# WlPK1_main.net
KiCad netlist of a schematic drawn in Altium Designer
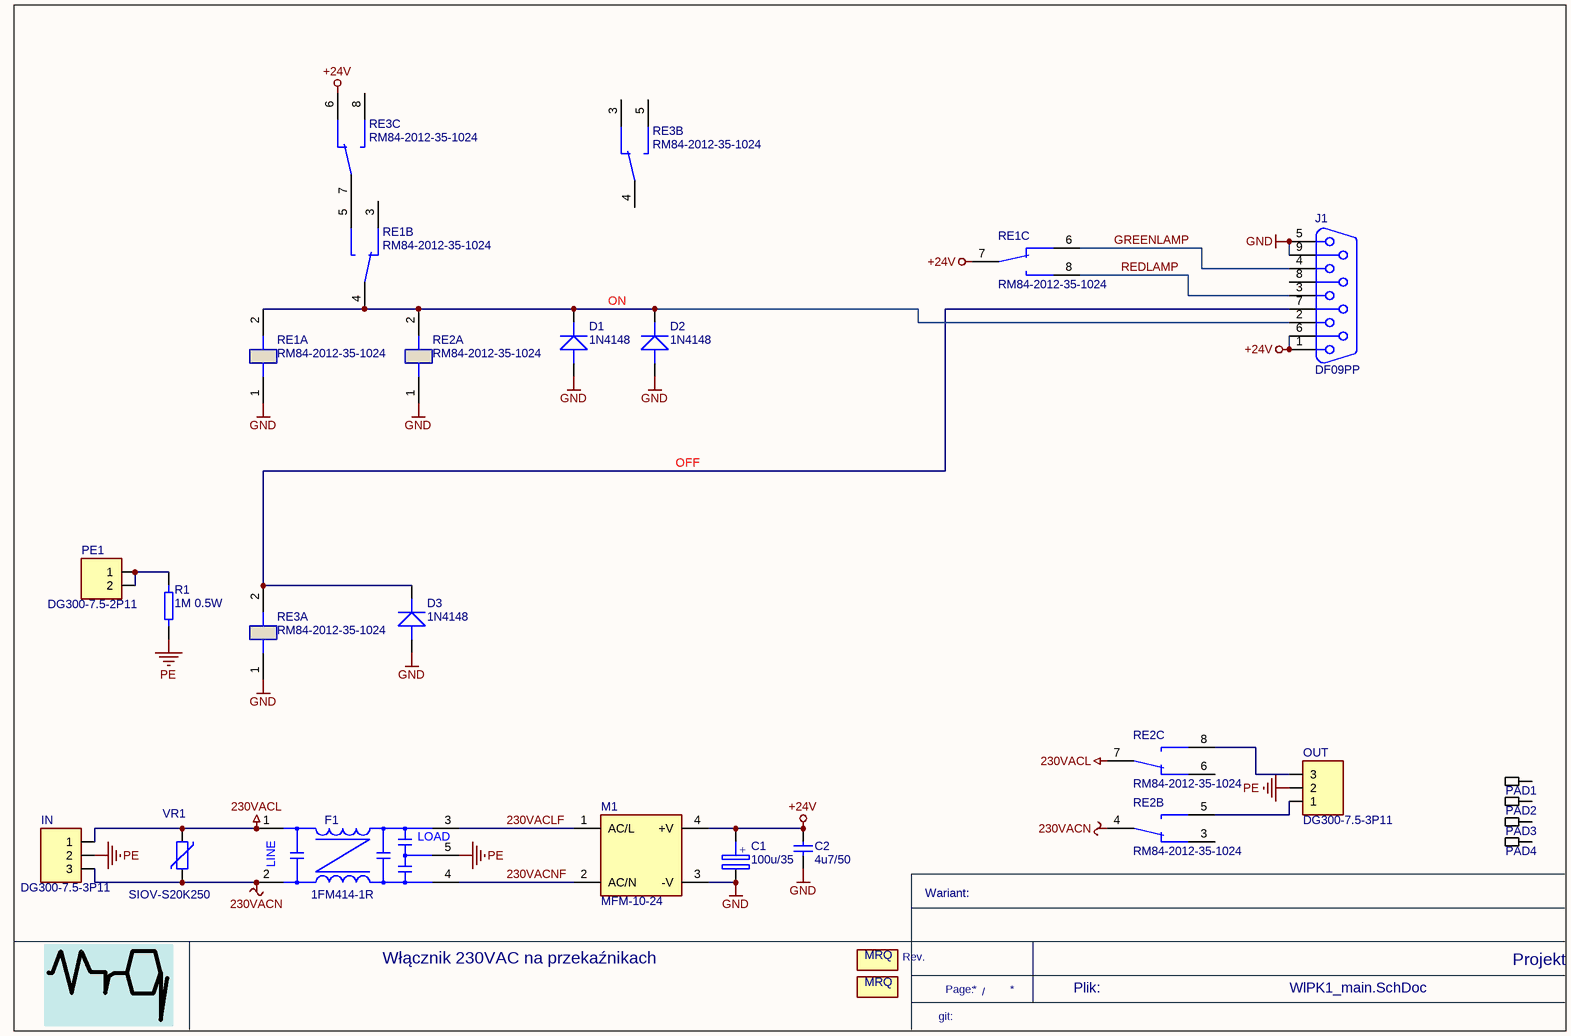
[diagram p0: WlPK1_main.SchDoc]

(export (version "E")
  (design (tool "Eeschema 10.0.6"))
  (components
    (comp (ref "C1") (value "100u/35") (footprint "CE1028") (libsource (lib "PartsMySQL") (part "CEL")))
    (comp (ref "C2") (value "4u7/50") (footprint "1210") (libsource (lib "PartsMySQL") (part "C")))
    (comp (ref "D1") (value "1N4148") (footprint "CE02") (libsource (lib "PartsMySQL") (part "DIODE")))
    (comp (ref "D2") (value "1N4148") (footprint "CE02") (libsource (lib "PartsMySQL") (part "DIODE")))
    (comp (ref "D3") (value "1N4148") (footprint "CE02") (libsource (lib "PartsMySQL") (part "DIODE")))
    (comp (ref "F1") (value "1FM414-1R") (footprint "1FM414") (libsource (lib "PartsMySQL") (part "1FM414")))
    (comp (ref "IN")
      (value "DG300-7.5-3P11")
      (footprint "DG300-7.5-3P11")
      (libsource (lib "") (part "HEADER3_1"))
    )
    (comp (ref "J1") (value "DF09PP") (footprint "DB9/F") (libsource (lib "PartsMySQL") (part "DB9")))
    (comp (ref "LOGO1")
      (value "MRQ_5")
      (footprint "MRQ_5_TL")
      (libsource (lib "PartsMySQL") (part "MRQLOGO"))
    )
    (comp (ref "LOGO2")
      (value "MRQ_5")
      (footprint "MRQ_5_TL")
      (libsource (lib "PartsMySQL") (part "MRQLOGO"))
    )
    (comp (ref "M1")
      (value "MFM-10-24")
      (footprint "MFM-10-24")
      (libsource (lib "PartsMySQL") (part "PM-10-5"))
    )
    (comp (ref "OUT")
      (value "DG300-7.5-3P11")
      (footprint "DG300-7.5-3P11")
      (libsource (lib "PartsMySQL") (part "HEADER3"))
    )
    (comp (ref "PAD1")
      (value "PAD3_5MM")
      (footprint "PAD3_5MM")
      (libsource (lib "PartsMySQL") (part "CLAMP_NOBOM"))
    )
    (comp (ref "PAD2")
      (value "PAD3_5MM")
      (footprint "PAD3_5MM")
      (libsource (lib "PartsMySQL") (part "CLAMP_NOBOM"))
    )
    (comp (ref "PAD3")
      (value "PAD3_5MM")
      (footprint "PAD3_5MM")
      (libsource (lib "PartsMySQL") (part "CLAMP_NOBOM"))
    )
    (comp (ref "PAD4")
      (value "PAD3_5MM")
      (footprint "PAD3_5MM")
      (libsource (lib "PartsMySQL") (part "CLAMP_NOBOM"))
    )
    (comp (ref "PE1")
      (value "DG300-7.5-2P11")
      (footprint "DG300-7.5-2P11")
      (libsource (lib "PartsMySQL") (part "HEADER2"))
    )
    (comp (ref "R1") (value "1M 0.5W") (footprint "R502816") (libsource (lib "PartsMySQL") (part "R")))
    (comp (ref "RE1") (value "RM84-2012-35-1024") (footprint "RM84-P") (libsource (lib "") (part "RM84-P_1")))
    (comp (ref "RE2")
      (value "RM84-2012-35-1024")
      (footprint "RM84-P")
      (libsource (lib "PartsMySQL") (part "RM84-P"))
    )
    (comp (ref "RE3")
      (value "RM84-2012-35-1024")
      (footprint "RM84-P")
      (libsource (lib "PartsMySQL") (part "RM84-P"))
    )
    (comp (ref "VR1")
      (value "SIOV-S20K250")
      (footprint "SIOV-S20K275")
      (libsource (lib "PartsMySQL") (part "VARISTOR"))
    )
  )
  (nets
    (net (code "1") (name "+24V") (class "Default")
      (node (ref "C1") (pin "2") (pinfunction "2_2") (pintype "passive"))
      (node (ref "C2") (pin "1") (pinfunction "1_1") (pintype "passive"))
      (node (ref "J1") (pin "1") (pinfunction "1_1") (pintype "passive"))
      (node (ref "J1") (pin "6") (pinfunction "6_6") (pintype "passive"))
      (node (ref "M1") (pin "4") (pinfunction "+V_4") (pintype "passive"))
      (node (ref "RE1") (pin "7") (pinfunction "11_7") (pintype "passive"))
      (node (ref "RE3") (pin "6") (pinfunction "12_6") (pintype "passive"))
    )
    (net (code "2") (name "/230VACLF") (class "Default")
      (node (ref "F1") (pin "3") (pinfunction "OUT2_3") (pintype "passive"))
      (node (ref "M1") (pin "1") (pinfunction "AC/L_1") (pintype "passive"))
    )
    (net (code "3") (name "/230VACNF") (class "Default")
      (node (ref "F1") (pin "4") (pinfunction "OUT1_4") (pintype "passive"))
      (node (ref "M1") (pin "2") (pinfunction "AC/N_2") (pintype "passive"))
    )
    (net (code "4") (name "/GREENLAMP") (class "Default")
      (node (ref "J1") (pin "4") (pinfunction "4_4") (pintype "passive"))
      (node (ref "RE1") (pin "6") (pinfunction "12_6") (pintype "passive"))
    )
    (net (code "5") (name "/OFF") (class "Default")
      (node (ref "D3") (pin "CATH") (pinfunction "CATH_CATH") (pintype "passive"))
      (node (ref "J1") (pin "7") (pinfunction "7_7") (pintype "passive"))
      (node (ref "RE3") (pin "2") (pinfunction "A2_2") (pintype "passive"))
    )
    (net (code "6") (name "/ON") (class "Default")
      (node (ref "D1") (pin "CATH") (pinfunction "CATH_CATH") (pintype "passive"))
      (node (ref "D2") (pin "CATH") (pinfunction "CATH_CATH") (pintype "passive"))
      (node (ref "J1") (pin "2") (pinfunction "2_2") (pintype "passive"))
      (node (ref "RE1") (pin "2") (pinfunction "A2_2") (pintype "passive"))
      (node (ref "RE1") (pin "4") (pinfunction "21_4") (pintype "passive"))
      (node (ref "RE2") (pin "2") (pinfunction "A2_2") (pintype "passive"))
    )
    (net (code "7") (name "/REDLAMP") (class "Default")
      (node (ref "J1") (pin "3") (pinfunction "3_3") (pintype "passive"))
      (node (ref "RE1") (pin "8") (pinfunction "14_8") (pintype "passive"))
    )
    (net (code "8") (name "230VACL") (class "Default")
      (node (ref "F1") (pin "1") (pinfunction "IN1_1") (pintype "passive"))
      (node (ref "IN") (pin "1") (pinfunction "1_1") (pintype "passive"))
      (node (ref "RE2") (pin "7") (pinfunction "11_7") (pintype "passive"))
      (node (ref "VR1") (pin "1") (pinfunction "1_1") (pintype "passive"))
    )
    (net (code "9") (name "230VACN") (class "Default")
      (node (ref "F1") (pin "2") (pinfunction "IN2_2") (pintype "passive"))
      (node (ref "IN") (pin "3") (pinfunction "3_3") (pintype "passive"))
      (node (ref "RE2") (pin "4") (pinfunction "21_4") (pintype "passive"))
      (node (ref "VR1") (pin "2") (pinfunction "2_2") (pintype "passive"))
    )
    (net (code "10") (name "GND") (class "Default")
      (node (ref "C1") (pin "1") (pinfunction "1_1") (pintype "passive"))
      (node (ref "C2") (pin "2") (pinfunction "2_2") (pintype "passive"))
      (node (ref "D1") (pin "ANOD") (pinfunction "ANOD_ANOD") (pintype "passive"))
      (node (ref "D2") (pin "ANOD") (pinfunction "ANOD_ANOD") (pintype "passive"))
      (node (ref "D3") (pin "ANOD") (pinfunction "ANOD_ANOD") (pintype "passive"))
      (node (ref "J1") (pin "5") (pinfunction "5_5") (pintype "passive"))
      (node (ref "J1") (pin "9") (pinfunction "9_9") (pintype "passive"))
      (node (ref "M1") (pin "3") (pinfunction "-V_3") (pintype "passive"))
      (node (ref "RE1") (pin "1") (pinfunction "A1_1") (pintype "passive"))
      (node (ref "RE2") (pin "1") (pinfunction "A1_1") (pintype "passive"))
      (node (ref "RE3") (pin "1") (pinfunction "A1_1") (pintype "passive"))
    )
    (net (code "11") (name "Net-(PE1-Pad1)") (class "Default")
      (node (ref "PE1") (pin "1") (pinfunction "1_1") (pintype "passive"))
      (node (ref "PE1") (pin "2") (pinfunction "2_2") (pintype "passive"))
      (node (ref "R1") (pin "2") (pinfunction "2_2") (pintype "passive"))
    )
    (net (code "12") (name "Net-(RE1B-24)") (class "Default")
      (node (ref "RE1") (pin "5") (pinfunction "24_5") (pintype "passive"))
      (node (ref "RE3") (pin "7") (pinfunction "11_7") (pintype "passive"))
    )
    (net (code "13") (name "Net-(RE2B-24)") (class "Default")
      (node (ref "OUT") (pin "1") (pinfunction "1_1") (pintype "passive"))
      (node (ref "RE2") (pin "5") (pinfunction "24_5") (pintype "passive"))
    )
    (net (code "14") (name "Net-(RE2C-14)") (class "Default")
      (node (ref "OUT") (pin "3") (pinfunction "3_3") (pintype "passive"))
      (node (ref "RE2") (pin "8") (pinfunction "14_8") (pintype "passive"))
    )
    (net (code "15") (name "PE") (class "Default")
      (node (ref "F1") (pin "5") (pinfunction "5_5") (pintype "passive"))
      (node (ref "IN") (pin "2") (pinfunction "2_2") (pintype "passive"))
      (node (ref "OUT") (pin "2") (pinfunction "2_2") (pintype "passive"))
      (node (ref "R1") (pin "1") (pinfunction "1_1") (pintype "passive"))
    )
    (net (code "16") (name "unconnected-(J1-Pad8)") (class "Default")
      (node (ref "J1") (pin "8") (pinfunction "8_8") (pintype "passive"))
    )
    (net (code "17") (name "unconnected-(PAD1-Pad1)") (class "Default")
      (node (ref "PAD1") (pin "1") (pinfunction "1_1") (pintype "passive"))
    )
    (net (code "18") (name "unconnected-(PAD2-Pad1)") (class "Default")
      (node (ref "PAD2") (pin "1") (pinfunction "1_1") (pintype "passive"))
    )
    (net (code "19") (name "unconnected-(PAD3-Pad1)") (class "Default")
      (node (ref "PAD3") (pin "1") (pinfunction "1_1") (pintype "passive"))
    )
    (net (code "20") (name "unconnected-(PAD4-Pad1)") (class "Default")
      (node (ref "PAD4") (pin "1") (pinfunction "1_1") (pintype "passive"))
    )
    (net (code "21") (name "unconnected-(RE1B-22-Pad3)") (class "Default")
      (node (ref "RE1") (pin "3") (pinfunction "22_3") (pintype "passive"))
    )
    (net (code "22") (name "unconnected-(RE2B-22-Pad3)") (class "Default")
      (node (ref "RE2") (pin "3") (pinfunction "22_3") (pintype "passive"))
    )
    (net (code "23") (name "unconnected-(RE2C-12-Pad6)") (class "Default")
      (node (ref "RE2") (pin "6") (pinfunction "12_6") (pintype "passive"))
    )
    (net (code "24") (name "unconnected-(RE3B-21-Pad4)") (class "Default")
      (node (ref "RE3") (pin "4") (pinfunction "21_4") (pintype "passive"))
    )
    (net (code "25") (name "unconnected-(RE3B-22-Pad3)") (class "Default")
      (node (ref "RE3") (pin "3") (pinfunction "22_3") (pintype "passive"))
    )
    (net (code "26") (name "unconnected-(RE3B-24-Pad5)") (class "Default")
      (node (ref "RE3") (pin "5") (pinfunction "24_5") (pintype "passive"))
    )
    (net (code "27") (name "unconnected-(RE3C-14-Pad8)") (class "Default")
      (node (ref "RE3") (pin "8") (pinfunction "14_8") (pintype "passive"))
    )
  )
)
